# TYPK.net
KiCad netlist of a schematic drawn in Altium Designer
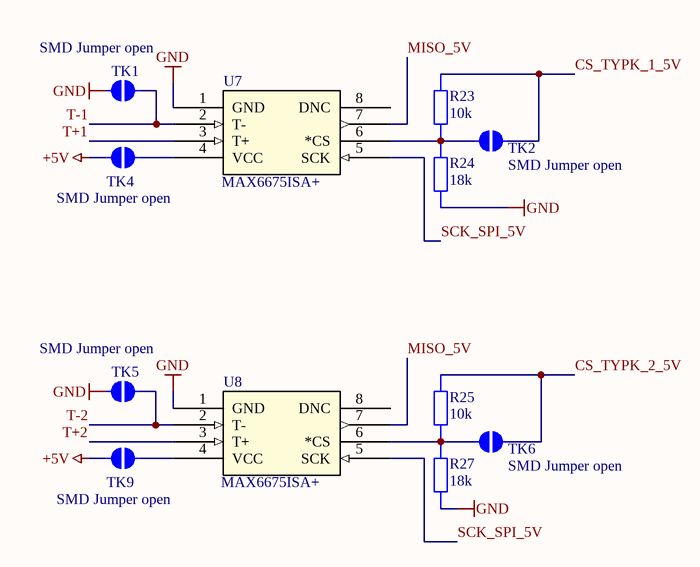
[diagram p0: TYPK.SchDoc]

(export (version "E")
  (design (tool "Eeschema 10.0.6"))
  (components
    (comp (ref "R23")
      (value "10k")
      (footprint "STACKPOLE CSR0603")
      (description "Resistor with multiple footprints")
      (fields (field (name "Comment") "SMD Resistor"))
      (libsource (lib "Standardbauteile") (part "SMD Resistor"))
    )
    (comp (ref "R24")
      (value "18k")
      (footprint "STACKPOLE CSR0603")
      (description "Resistor with multiple footprints")
      (fields (field (name "Comment") "SMD Resistor"))
      (libsource (lib "Standardbauteile") (part "SMD Resistor"))
    )
    (comp (ref "R25")
      (value "10k")
      (footprint "STACKPOLE CSR0603")
      (description "Resistor with multiple footprints")
      (fields (field (name "Comment") "SMD Resistor"))
      (libsource (lib "Standardbauteile") (part "SMD Resistor"))
    )
    (comp (ref "R27")
      (value "18k")
      (footprint "STACKPOLE CSR0603")
      (description "Resistor with multiple footprints")
      (fields (field (name "Comment") "SMD Resistor"))
      (libsource (lib "Standardbauteile") (part "SMD Resistor"))
    )
    (comp (ref "TK1")
      (value "SMD Jumper open")
      (footprint "SMD-JUMPER-OPEN")
      (libsource (lib "Standardbauteile") (part "SMD Jumper open"))
    )
    (comp (ref "TK2")
      (value "SMD Jumper open")
      (footprint "SMD-JUMPER-OPEN")
      (libsource (lib "Standardbauteile") (part "SMD Jumper open"))
    )
    (comp (ref "TK4")
      (value "SMD Jumper open")
      (footprint "SMD-JUMPER-OPEN")
      (libsource (lib "Standardbauteile") (part "SMD Jumper open"))
    )
    (comp (ref "TK5")
      (value "SMD Jumper open")
      (footprint "SMD-JUMPER-OPEN")
      (libsource (lib "Standardbauteile") (part "SMD Jumper open"))
    )
    (comp (ref "TK6")
      (value "SMD Jumper open")
      (footprint "SMD-JUMPER-OPEN")
      (libsource (lib "Standardbauteile") (part "SMD Jumper open"))
    )
    (comp (ref "TK9")
      (value "SMD Jumper open")
      (footprint "SMD-JUMPER-OPEN")
      (libsource (lib "Standardbauteile") (part "SMD Jumper open"))
    )
    (comp (ref "U7")
      (value "MAX6675ISA+")
      (footprint "SOIC8")
      (description "No Description Available")
      (fields
        (field (name "MANUFACTURER_PART_NUMBER") "MAX31855KASA+")
        (field (name "COPYRIGHT") "Copyright (C) 2018 Accelerated Designs. All rights reserved")
      )
      (libsource (lib "Eric") (part "MAX31855KASA+"))
    )
    (comp (ref "U8")
      (value "MAX6675ISA+")
      (footprint "SOIC8")
      (description "No Description Available")
      (fields
        (field (name "MANUFACTURER_PART_NUMBER") "MAX31855KASA+")
        (field (name "COPYRIGHT") "Copyright (C) 2018 Accelerated Designs. All rights reserved")
      )
      (libsource (lib "Eric") (part "MAX31855KASA+"))
    )
  )
  (nets
    (net (code "1") (name "+5V") (class "Default")
      (node (ref "TK4") (pin "1") (pinfunction "1_1") (pintype "passive"))
      (node (ref "TK9") (pin "1") (pinfunction "1_1") (pintype "passive"))
    )
    (net (code "2") (name "/CS_TYPK_1_5V") (class "Default")
      (node (ref "R23") (pin "2") (pinfunction "2_2") (pintype "passive"))
      (node (ref "TK2") (pin "2") (pinfunction "2_2") (pintype "passive"))
    )
    (net (code "3") (name "/CS_TYPK_2_5V") (class "Default")
      (node (ref "R25") (pin "2") (pinfunction "2_2") (pintype "passive"))
      (node (ref "TK6") (pin "2") (pinfunction "2_2") (pintype "passive"))
    )
    (net (code "4") (name "/MISO_5V") (class "Default")
      (node (ref "U7") (pin "7") (pinfunction "SO_7") (pintype "output"))
      (node (ref "U8") (pin "7") (pinfunction "SO_7") (pintype "output"))
    )
    (net (code "5") (name "/SCK_SPI_5V") (class "Default")
      (node (ref "U7") (pin "5") (pinfunction "SCK_5") (pintype "input"))
      (node (ref "U8") (pin "5") (pinfunction "SCK_5") (pintype "input"))
    )
    (net (code "6") (name "/T+1") (class "Default")
      (node (ref "U7") (pin "3") (pinfunction "T+_3") (pintype "input"))
    )
    (net (code "7") (name "/T+2") (class "Default")
      (node (ref "U8") (pin "3") (pinfunction "T+_3") (pintype "input"))
    )
    (net (code "8") (name "/T-1") (class "Default")
      (node (ref "TK1") (pin "2") (pinfunction "2_2") (pintype "passive"))
      (node (ref "U7") (pin "2") (pinfunction "T-_2") (pintype "input"))
    )
    (net (code "9") (name "/T-2") (class "Default")
      (node (ref "TK5") (pin "2") (pinfunction "2_2") (pintype "passive"))
      (node (ref "U8") (pin "2") (pinfunction "T-_2") (pintype "input"))
    )
    (net (code "10") (name "GND") (class "Default")
      (node (ref "R24") (pin "1") (pinfunction "1_1") (pintype "passive"))
      (node (ref "R27") (pin "1") (pinfunction "1_1") (pintype "passive"))
      (node (ref "TK1") (pin "1") (pinfunction "1_1") (pintype "passive"))
      (node (ref "TK5") (pin "1") (pinfunction "1_1") (pintype "passive"))
      (node (ref "U7") (pin "1") (pinfunction "GND_1") (pintype "power_in"))
      (node (ref "U8") (pin "1") (pinfunction "GND_1") (pintype "power_in"))
    )
    (net (code "11") (name "Net-(U7-*CS)") (class "Default")
      (node (ref "R23") (pin "1") (pinfunction "1_1") (pintype "passive"))
      (node (ref "R24") (pin "2") (pinfunction "2_2") (pintype "passive"))
      (node (ref "TK2") (pin "1") (pinfunction "1_1") (pintype "passive"))
      (node (ref "U7") (pin "6") (pinfunction "*CS_6") (pintype "passive"))
    )
    (net (code "12") (name "Net-(U7-VCC)") (class "Default")
      (node (ref "TK4") (pin "2") (pinfunction "2_2") (pintype "passive"))
      (node (ref "U7") (pin "4") (pinfunction "VCC_4") (pintype "power_in"))
    )
    (net (code "13") (name "Net-(U8-*CS)") (class "Default")
      (node (ref "R25") (pin "1") (pinfunction "1_1") (pintype "passive"))
      (node (ref "R27") (pin "2") (pinfunction "2_2") (pintype "passive"))
      (node (ref "TK6") (pin "1") (pinfunction "1_1") (pintype "passive"))
      (node (ref "U8") (pin "6") (pinfunction "*CS_6") (pintype "passive"))
    )
    (net (code "14") (name "Net-(U8-VCC)") (class "Default")
      (node (ref "TK9") (pin "2") (pinfunction "2_2") (pintype "passive"))
      (node (ref "U8") (pin "4") (pinfunction "VCC_4") (pintype "power_in"))
    )
    (net (code "15") (name "unconnected-(U7-DNC-Pad8)") (class "Default")
      (node (ref "U7") (pin "8") (pinfunction "DNC_8") (pintype "passive"))
    )
    (net (code "16") (name "unconnected-(U8-DNC-Pad8)") (class "Default")
      (node (ref "U8") (pin "8") (pinfunction "DNC_8") (pintype "passive"))
    )
  )
)
